# bpod_stepper_1_2.net
KiCad netlist of a schematic drawn in EAGLE
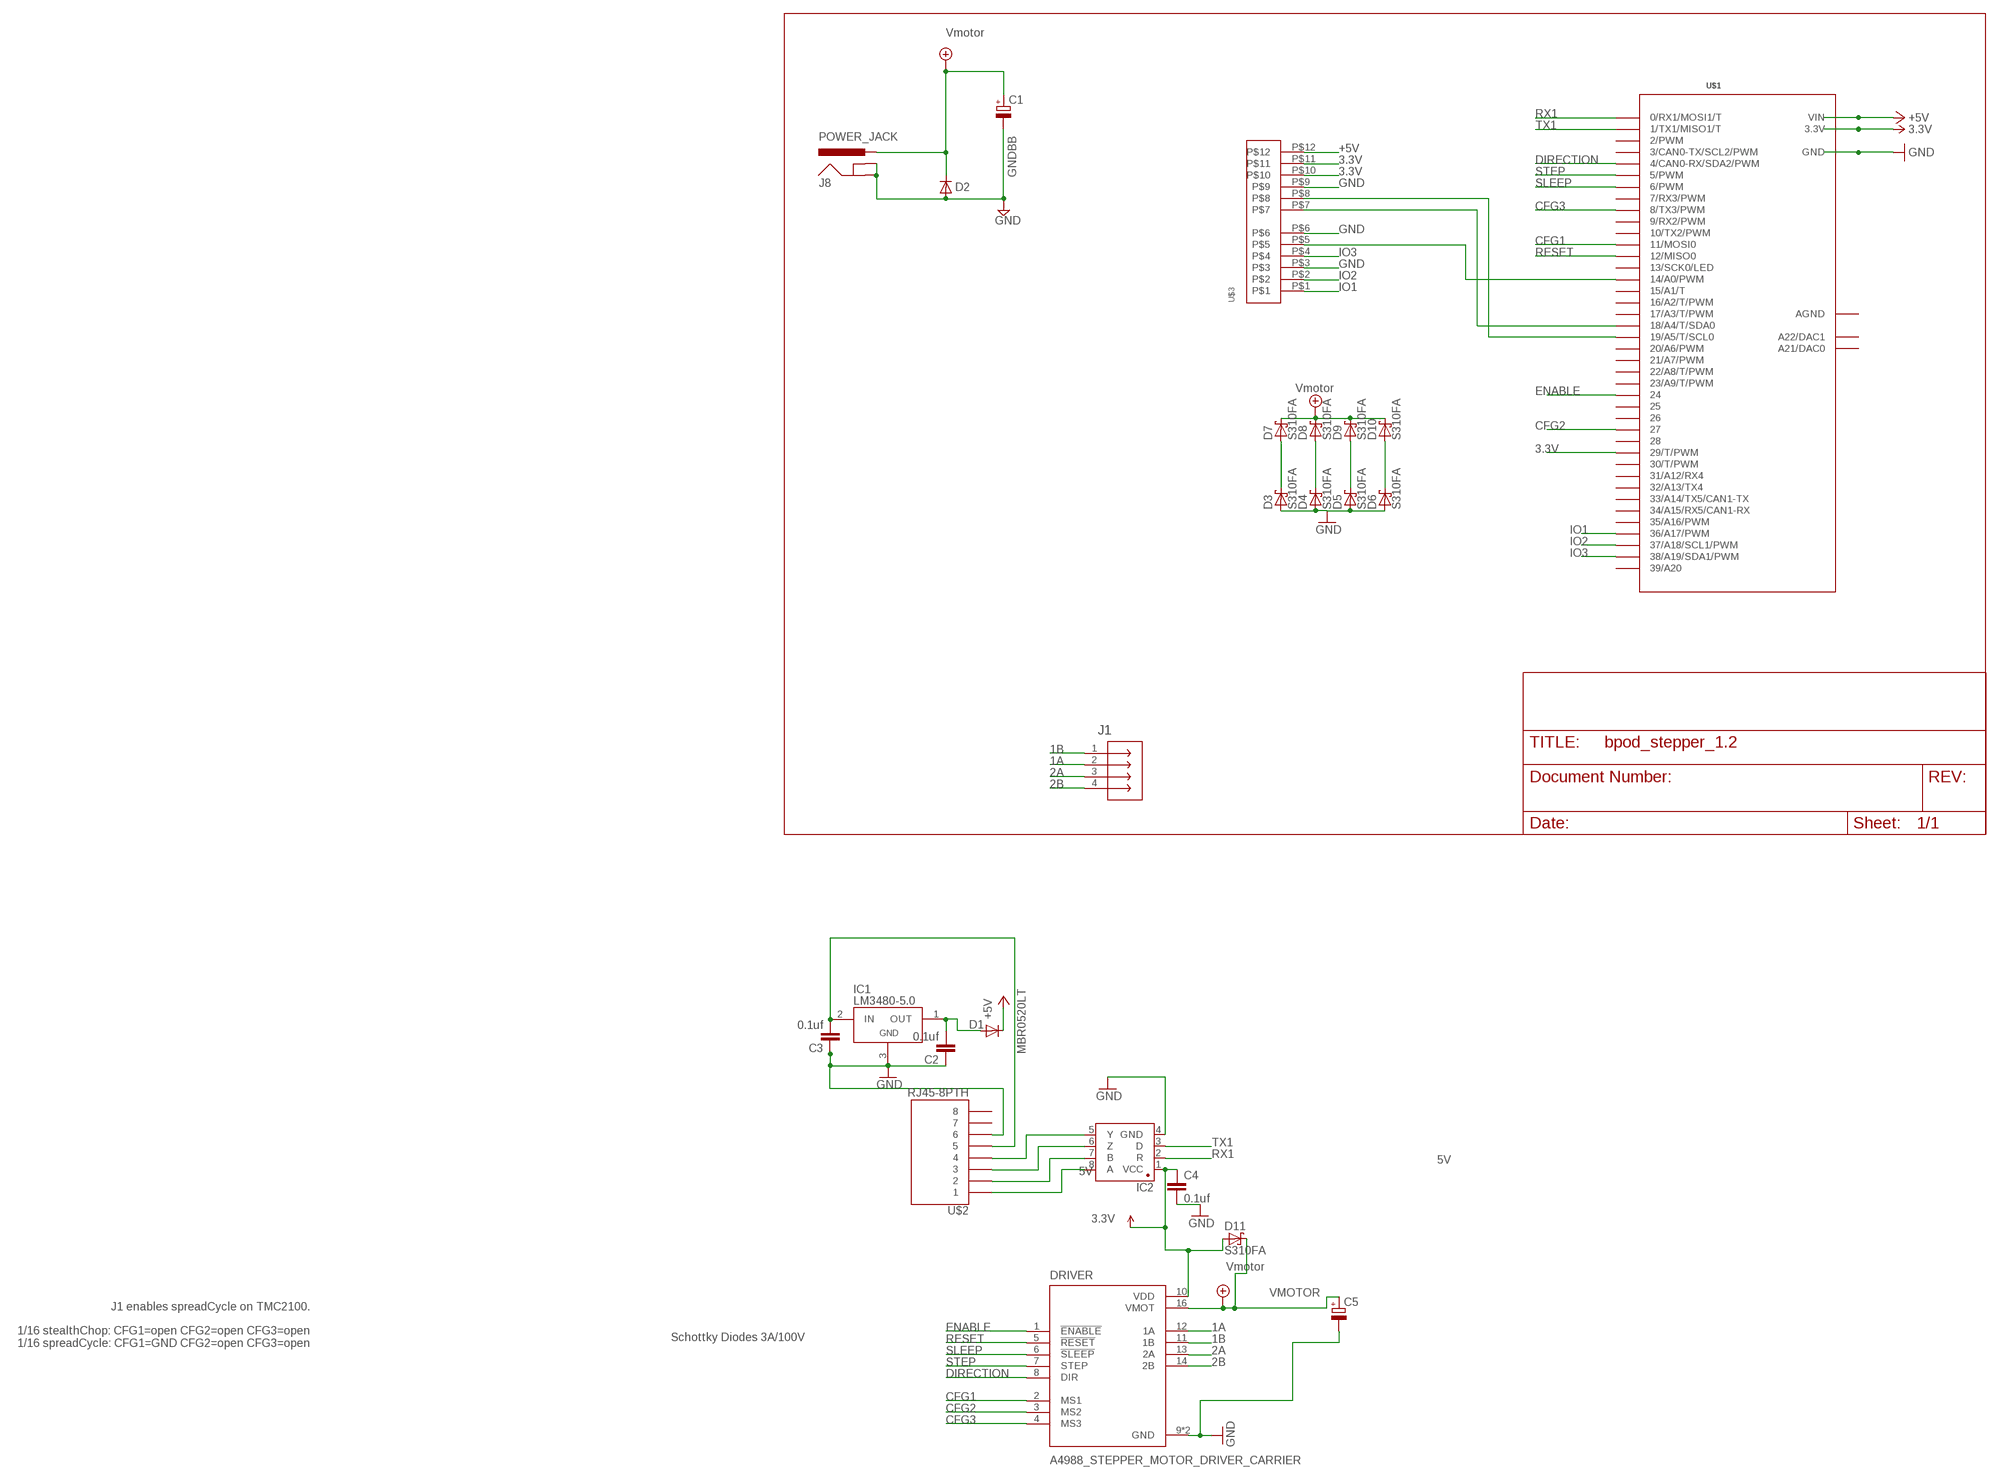
[diagram p0: schematic, sheet 1]

(export (version "E")
  (design (tool "Eeschema 10.0.6"))
  (components
    (comp (ref "C1")
      (value "CPOL-EUG")
      (footprint "eagle-import:PANASONIC_G")
      (libsource (lib "eagle-import") (part "CPOL-EUG"))
    )
    (comp (ref "C2")
      (value "0.1uf")
      (footprint "eagle-import:1206@1")
      (libsource (lib "eagle-import") (part "CAP1206"))
    )
    (comp (ref "C3")
      (value "0.1uf")
      (footprint "eagle-import:1206@1")
      (libsource (lib "eagle-import") (part "CAP1206"))
    )
    (comp (ref "C4")
      (value "0.1uf")
      (footprint "eagle-import:1206@1")
      (libsource (lib "eagle-import") (part "CAP1206"))
    )
    (comp (ref "C5")
      (value "CPOL-EUG")
      (footprint "eagle-import:PANASONIC_G")
      (libsource (lib "eagle-import") (part "CPOL-EUG"))
    )
    (comp (ref "D1")
      (value "MBR0520LT")
      (footprint "eagle-import:SOD123")
      (libsource (lib "eagle-import") (part "MBR0520LT"))
    )
    (comp (ref "D2")
      (value "DIODE-DO214AA")
      (footprint "eagle-import:DO214AA")
      (libsource (lib "eagle-import") (part "DIODE-DO214AA"))
    )
    (comp (ref "D3")
      (value "S310FA")
      (footprint "eagle-import:SOD123")
      (libsource (lib "eagle-import") (part "D_SCHOTTKY-SOD123"))
    )
    (comp (ref "D4")
      (value "S310FA")
      (footprint "eagle-import:SOD123")
      (libsource (lib "eagle-import") (part "D_SCHOTTKY-SOD123"))
    )
    (comp (ref "D5")
      (value "S310FA")
      (footprint "eagle-import:SOD123")
      (libsource (lib "eagle-import") (part "D_SCHOTTKY-SOD123"))
    )
    (comp (ref "D6")
      (value "S310FA")
      (footprint "eagle-import:SOD123")
      (libsource (lib "eagle-import") (part "D_SCHOTTKY-SOD123"))
    )
    (comp (ref "D7")
      (value "S310FA")
      (footprint "eagle-import:SOD123")
      (libsource (lib "eagle-import") (part "D_SCHOTTKY-SOD123"))
    )
    (comp (ref "D8")
      (value "S310FA")
      (footprint "eagle-import:SOD123")
      (libsource (lib "eagle-import") (part "D_SCHOTTKY-SOD123"))
    )
    (comp (ref "D9")
      (value "S310FA")
      (footprint "eagle-import:SOD123")
      (libsource (lib "eagle-import") (part "D_SCHOTTKY-SOD123"))
    )
    (comp (ref "D10")
      (value "S310FA")
      (footprint "eagle-import:SOD123")
      (libsource (lib "eagle-import") (part "D_SCHOTTKY-SOD123"))
    )
    (comp (ref "D11")
      (value "S310FA")
      (footprint "eagle-import:SOD123")
      (libsource (lib "eagle-import") (part "D_SCHOTTKY-SOD123"))
    )
    (comp (ref "DRIVER")
      (value "A4988_STEPPER_MOTOR_DRIVER_CARRIER")
      (footprint "eagle-import:MODULE_A4988_STEPPER_MOTOR_DRIVER_CARRIER")
      (fields (field (name "MF") "Pololu") (field (name "MP") "A4988 STEPPER MOTOR DRIVER CARRIER"))
      (libsource (lib "eagle-import") (part "A4988_STEPPER_MOTOR_DRIVER_CARRIER"))
    )
    (comp (ref "IC1")
      (value "LM3480-5.0")
      (footprint "eagle-import:SOT-23-3")
      (libsource (lib "eagle-import") (part "LM3480-5.0"))
    )
    (comp (ref "IC2")
      (value "SN65HVD31DR")
      (footprint "eagle-import:SO08")
      (libsource (lib "eagle-import") (part "SN65HVD31DR"))
    )
    (comp (ref "J1")
      (value "282841-4")
      (footprint "eagle-import:CONN4_282841-4_TEC")
      (fields (field (name "COPYRIGHT") "Copyright (C) 2018 Accelerated Designs. All rights reserved"))
      (libsource (lib "eagle-import") (part "282841-4"))
    )
    (comp (ref "J8")
      (value "POWER_JACK")
      (footprint "eagle-import:POWER_JACK_PTH")
      (libsource (lib "eagle-import") (part "POWER_JACK"))
    )
    (comp (ref "U$1")
      (value "TEENSY_3.6_DIL")
      (footprint "eagle-import:TEENSY_3.6_DIL")
      (libsource (lib "eagle-import") (part "TEENSY_3.6_DIL"))
    )
    (comp (ref "U$2")
      (value "RJ45-8PTH")
      (footprint "eagle-import:RJ45-8")
      (libsource (lib "eagle-import") (part "RJ45-8PTH"))
    )
    (comp (ref "U$3")
      (value "12POS_MOLEX_SOCKET")
      (footprint "eagle-import:12POS_MOLEX_SOCKET")
      (libsource (lib "eagle-import") (part "12POS_MOLEX_SOCKET"))
    )
  )
  (nets
    (net (code "1") (name "+5V") (class "Default")
      (node (ref "D1") (pin "C") (pinfunction "C_C") (pintype "passive"))
      (node (ref "U$1") (pin "VIN") (pinfunction "VIN_VIN") (pintype "power_in"))
      (node (ref "U$3") (pin "P$12") (pinfunction "P$12_P$12") (pintype "bidirectional"))
    )
    (net (code "2") (name "/1A") (class "Default")
      (node (ref "D4") (pin "C") (pinfunction "C_C") (pintype "passive"))
      (node (ref "D8") (pin "A") (pinfunction "A_A") (pintype "passive"))
      (node (ref "DRIVER") (pin "12") (pinfunction "1A_12") (pintype "output"))
      (node (ref "J1") (pin "2") (pinfunction "2_2") (pintype "passive"))
    )
    (net (code "3") (name "/1B") (class "Default")
      (node (ref "D3") (pin "C") (pinfunction "C_C") (pintype "passive"))
      (node (ref "D7") (pin "A") (pinfunction "A_A") (pintype "passive"))
      (node (ref "DRIVER") (pin "11") (pinfunction "1B_11") (pintype "output"))
      (node (ref "J1") (pin "1") (pinfunction "1_1") (pintype "passive"))
    )
    (net (code "4") (name "/2A") (class "Default")
      (node (ref "D5") (pin "C") (pinfunction "C_C") (pintype "passive"))
      (node (ref "D9") (pin "A") (pinfunction "A_A") (pintype "passive"))
      (node (ref "DRIVER") (pin "13") (pinfunction "2A_13") (pintype "output"))
      (node (ref "J1") (pin "3") (pinfunction "3_3") (pintype "passive"))
    )
    (net (code "5") (name "/2B") (class "Default")
      (node (ref "D10") (pin "A") (pinfunction "A_A") (pintype "passive"))
      (node (ref "D6") (pin "C") (pinfunction "C_C") (pintype "passive"))
      (node (ref "DRIVER") (pin "14") (pinfunction "2B_14") (pintype "output"))
      (node (ref "J1") (pin "4") (pinfunction "4_4") (pintype "passive"))
    )
    (net (code "6") (name "/AGND") (class "Default")
      (node (ref "U$1") (pin "AGND") (pinfunction "AGND_AGND") (pintype "power_in"))
    )
    (net (code "7") (name "/CFG1") (class "Default")
      (node (ref "DRIVER") (pin "2") (pinfunction "MS1_2") (pintype "input"))
      (node (ref "U$1") (pin "11") (pinfunction "11/MOSI0_11") (pintype "bidirectional"))
    )
    (net (code "8") (name "/CFG2") (class "Default")
      (node (ref "DRIVER") (pin "3") (pinfunction "MS2_3") (pintype "input"))
      (node (ref "U$1") (pin "27") (pinfunction "27_27") (pintype "bidirectional"))
    )
    (net (code "9") (name "/CFG3") (class "Default")
      (node (ref "DRIVER") (pin "4") (pinfunction "MS3_4") (pintype "input"))
      (node (ref "U$1") (pin "8") (pinfunction "8/TX3/PWM_8") (pintype "bidirectional"))
    )
    (net (code "10") (name "/DIRECTION") (class "Default")
      (node (ref "DRIVER") (pin "8") (pinfunction "DIR_8") (pintype "input"))
      (node (ref "U$1") (pin "4") (pinfunction "4/CAN0-RX/SDA2/PWM_4") (pintype "bidirectional"))
    )
    (net (code "11") (name "/ENABLE") (class "Default")
      (node (ref "DRIVER") (pin "1") (pinfunction "~{ENABLE}_1") (pintype "input"))
      (node (ref "U$1") (pin "24") (pinfunction "24_24") (pintype "bidirectional"))
    )
    (net (code "12") (name "/IO1") (class "Default")
      (node (ref "U$1") (pin "36/A17") (pinfunction "36/A17/PWM_36/A17") (pintype "bidirectional"))
      (node (ref "U$3") (pin "P$1") (pinfunction "P$1_P$1") (pintype "bidirectional"))
    )
    (net (code "13") (name "/IO2") (class "Default")
      (node (ref "U$1") (pin "37/A18") (pinfunction "37/A18/SCL1/PWM_37/A18") (pintype "bidirectional"))
      (node (ref "U$3") (pin "P$2") (pinfunction "P$2_P$2") (pintype "bidirectional"))
    )
    (net (code "14") (name "/IO3") (class "Default")
      (node (ref "U$1") (pin "38/A19") (pinfunction "38/A19/SDA1/PWM_38/A19") (pintype "bidirectional"))
      (node (ref "U$3") (pin "P$4") (pinfunction "P$4_P$4") (pintype "bidirectional"))
    )
    (net (code "15") (name "/RESET") (class "Default")
      (node (ref "DRIVER") (pin "5") (pinfunction "~{RESET}_5") (pintype "input"))
      (node (ref "U$1") (pin "12") (pinfunction "12/MISO0_12") (pintype "bidirectional"))
    )
    (net (code "16") (name "/RX1") (class "Default")
      (node (ref "IC2") (pin "2") (pinfunction "R_2") (pintype "bidirectional"))
      (node (ref "U$1") (pin "0") (pinfunction "0/RX1/MOSI1/T_0") (pintype "bidirectional"))
    )
    (net (code "17") (name "/SLEEP") (class "Default")
      (node (ref "DRIVER") (pin "6") (pinfunction "~{SLEEP}_6") (pintype "input"))
      (node (ref "U$1") (pin "6") (pinfunction "6/PWM_6") (pintype "bidirectional"))
    )
    (net (code "18") (name "/STEP") (class "Default")
      (node (ref "DRIVER") (pin "7") (pinfunction "STEP_7") (pintype "input"))
      (node (ref "U$1") (pin "5") (pinfunction "5/PWM_5") (pintype "bidirectional"))
    )
    (net (code "19") (name "/TX1") (class "Default")
      (node (ref "IC2") (pin "3") (pinfunction "D_3") (pintype "bidirectional"))
      (node (ref "U$1") (pin "1") (pinfunction "1/TX1/MISO1/T_1") (pintype "bidirectional"))
    )
    (net (code "20") (name "3.3V") (class "Default")
      (node (ref "C4") (pin "1") (pinfunction "1_1") (pintype "passive"))
      (node (ref "D11") (pin "A") (pinfunction "A_A") (pintype "passive"))
      (node (ref "DRIVER") (pin "10") (pinfunction "VDD_10") (pintype "power_in"))
      (node (ref "IC2") (pin "1") (pinfunction "VCC_1") (pintype "bidirectional"))
      (node (ref "U$1") (pin "29") (pinfunction "29/T/PWM_29") (pintype "bidirectional"))
      (node (ref "U$1") (pin "3.3V") (pinfunction "3.3V_3.3V") (pintype "power_in"))
      (node (ref "U$1") (pin "3.3V3") (pinfunction "3.3V_3.3V3") (pintype "power_in"))
      (node (ref "U$3") (pin "P$10") (pinfunction "P$10_P$10") (pintype "bidirectional"))
      (node (ref "U$3") (pin "P$11") (pinfunction "P$11_P$11") (pintype "bidirectional"))
    )
    (net (code "21") (name "GND") (class "Default")
      (node (ref "C1") (pin "-") (pinfunction "-_-") (pintype "passive"))
      (node (ref "C2") (pin "1") (pinfunction "1_1") (pintype "passive"))
      (node (ref "C3") (pin "1") (pinfunction "1_1") (pintype "passive"))
      (node (ref "C4") (pin "2") (pinfunction "2_2") (pintype "passive"))
      (node (ref "C5") (pin "-") (pinfunction "-_-") (pintype "passive"))
      (node (ref "D2") (pin "A") (pinfunction "A_A") (pintype "passive"))
      (node (ref "D3") (pin "A") (pinfunction "A_A") (pintype "passive"))
      (node (ref "D4") (pin "A") (pinfunction "A_A") (pintype "passive"))
      (node (ref "D5") (pin "A") (pinfunction "A_A") (pintype "passive"))
      (node (ref "D6") (pin "A") (pinfunction "A_A") (pintype "passive"))
      (node (ref "DRIVER") (pin "15") (pinfunction "GND_15") (pintype "power_in"))
      (node (ref "DRIVER") (pin "9") (pinfunction "GND_9") (pintype "power_in"))
      (node (ref "IC1") (pin "3") (pinfunction "GND_3") (pintype "power_in"))
      (node (ref "IC2") (pin "4") (pinfunction "GND_4") (pintype "bidirectional"))
      (node (ref "J8") (pin "GND") (pinfunction "GND_GND") (pintype "bidirectional"))
      (node (ref "J8") (pin "GNDBREAK") (pinfunction "GNDBREAK_GNDBREAK") (pintype "bidirectional"))
      (node (ref "U$1") (pin "GND") (pinfunction "GND_GND") (pintype "power_in"))
      (node (ref "U$1") (pin "GND1") (pinfunction "GND_GND1") (pintype "power_in"))
      (node (ref "U$2") (pin "6") (pinfunction "6_6") (pintype "bidirectional"))
      (node (ref "U$3") (pin "P$3") (pinfunction "P$3_P$3") (pintype "bidirectional"))
      (node (ref "U$3") (pin "P$6") (pinfunction "P$6_P$6") (pintype "bidirectional"))
      (node (ref "U$3") (pin "P$9") (pinfunction "P$9_P$9") (pintype "bidirectional"))
    )
    (net (code "22") (name "Net-(IC1-IN)") (class "Default")
      (node (ref "C3") (pin "2") (pinfunction "2_2") (pintype "passive"))
      (node (ref "IC1") (pin "2") (pinfunction "IN_2") (pintype "power_in"))
      (node (ref "U$2") (pin "5") (pinfunction "5_5") (pintype "bidirectional"))
    )
    (net (code "23") (name "Net-(IC1-OUT)") (class "Default")
      (node (ref "C2") (pin "2") (pinfunction "2_2") (pintype "passive"))
      (node (ref "D1") (pin "A") (pinfunction "A_A") (pintype "passive"))
      (node (ref "IC1") (pin "1") (pinfunction "OUT_1") (pintype "power_in"))
    )
    (net (code "24") (name "Net-(IC2-A)") (class "Default")
      (node (ref "IC2") (pin "8") (pinfunction "A_8") (pintype "bidirectional"))
      (node (ref "U$2") (pin "1") (pinfunction "1_1") (pintype "bidirectional"))
    )
    (net (code "25") (name "Net-(IC2-B)") (class "Default")
      (node (ref "IC2") (pin "7") (pinfunction "B_7") (pintype "bidirectional"))
      (node (ref "U$2") (pin "2") (pinfunction "2_2") (pintype "bidirectional"))
    )
    (net (code "26") (name "Net-(IC2-Y)") (class "Default")
      (node (ref "IC2") (pin "5") (pinfunction "Y_5") (pintype "bidirectional"))
      (node (ref "U$2") (pin "4") (pinfunction "4_4") (pintype "bidirectional"))
    )
    (net (code "27") (name "Net-(IC2-Z)") (class "Default")
      (node (ref "IC2") (pin "6") (pinfunction "Z_6") (pintype "bidirectional"))
      (node (ref "U$2") (pin "3") (pinfunction "3_3") (pintype "bidirectional"))
    )
    (net (code "28") (name "Net-(U$1-14{slash}A0{slash}PWM)") (class "Default")
      (node (ref "U$1") (pin "14/A0") (pinfunction "14/A0/PWM_14/A0") (pintype "bidirectional"))
      (node (ref "U$3") (pin "P$5") (pinfunction "P$5_P$5") (pintype "bidirectional"))
    )
    (net (code "29") (name "Net-(U$1-18{slash}A4{slash}T{slash}SDA0)") (class "Default")
      (node (ref "U$1") (pin "18/A4") (pinfunction "18/A4/T/SDA0_18/A4") (pintype "bidirectional"))
      (node (ref "U$3") (pin "P$7") (pinfunction "P$7_P$7") (pintype "bidirectional"))
    )
    (net (code "30") (name "Net-(U$1-19{slash}A5{slash}T{slash}SCL0)") (class "Default")
      (node (ref "U$1") (pin "19/A5") (pinfunction "19/A5/T/SCL0_19/A5") (pintype "bidirectional"))
      (node (ref "U$3") (pin "P$8") (pinfunction "P$8_P$8") (pintype "bidirectional"))
    )
    (net (code "31") (name "Vmotor") (class "Default")
      (node (ref "C1") (pin "+") (pinfunction "+_+") (pintype "passive"))
      (node (ref "C5") (pin "+") (pinfunction "+_+") (pintype "passive"))
      (node (ref "D10") (pin "C") (pinfunction "C_C") (pintype "passive"))
      (node (ref "D11") (pin "C") (pinfunction "C_C") (pintype "passive"))
      (node (ref "D2") (pin "C") (pinfunction "C_C") (pintype "passive"))
      (node (ref "D7") (pin "C") (pinfunction "C_C") (pintype "passive"))
      (node (ref "D8") (pin "C") (pinfunction "C_C") (pintype "passive"))
      (node (ref "D9") (pin "C") (pinfunction "C_C") (pintype "passive"))
      (node (ref "DRIVER") (pin "16") (pinfunction "VMOT_16") (pintype "power_in"))
      (node (ref "J8") (pin "PWR") (pinfunction "PWR_PWR") (pintype "bidirectional"))
    )
    (net (code "32") (name "unconnected-(U$1-2{slash}PWM-Pad2)") (class "Default")
      (node (ref "U$1") (pin "2") (pinfunction "2/PWM_2") (pintype "bidirectional"))
    )
    (net (code "33") (name "unconnected-(U$1-3{slash}CAN0-TX{slash}SCL2{slash}PWM-Pad3)") (class "Default")
      (node (ref "U$1") (pin "3") (pinfunction "3/CAN0-TX/SCL2/PWM_3") (pintype "bidirectional"))
    )
    (net (code "34") (name "unconnected-(U$1-7{slash}RX3{slash}PWM-Pad7)") (class "Default")
      (node (ref "U$1") (pin "7") (pinfunction "7/RX3/PWM_7") (pintype "bidirectional"))
    )
    (net (code "35") (name "unconnected-(U$1-9{slash}RX2{slash}PWM-Pad9)") (class "Default")
      (node (ref "U$1") (pin "9") (pinfunction "9/RX2/PWM_9") (pintype "bidirectional"))
    )
    (net (code "36") (name "unconnected-(U$1-10{slash}TX2{slash}PWM-Pad10)") (class "Default")
      (node (ref "U$1") (pin "10") (pinfunction "10/TX2/PWM_10") (pintype "bidirectional"))
    )
    (net (code "37") (name "unconnected-(U$1-13{slash}SCK0{slash}LED-Pad13)") (class "Default")
      (node (ref "U$1") (pin "13") (pinfunction "13/SCK0/LED_13") (pintype "bidirectional"))
    )
    (net (code "38") (name "unconnected-(U$1-15{slash}A1{slash}T-Pad15{slash}A1)") (class "Default")
      (node (ref "U$1") (pin "15/A1") (pinfunction "15/A1/T_15/A1") (pintype "bidirectional"))
    )
    (net (code "39") (name "unconnected-(U$1-16{slash}A2{slash}T{slash}PWM-Pad16{slash}A2)") (class "Default")
      (node (ref "U$1") (pin "16/A2") (pinfunction "16/A2/T/PWM_16/A2") (pintype "bidirectional"))
    )
    (net (code "40") (name "unconnected-(U$1-17{slash}A3{slash}T{slash}PWM-Pad17{slash}A3)") (class "Default")
      (node (ref "U$1") (pin "17/A3") (pinfunction "17/A3/T/PWM_17/A3") (pintype "bidirectional"))
    )
    (net (code "41") (name "unconnected-(U$1-20{slash}A6{slash}PWM-Pad20{slash}A6)") (class "Default")
      (node (ref "U$1") (pin "20/A6") (pinfunction "20/A6/PWM_20/A6") (pintype "bidirectional"))
    )
    (net (code "42") (name "unconnected-(U$1-21{slash}A7{slash}PWM-Pad21{slash}A7)") (class "Default")
      (node (ref "U$1") (pin "21/A7") (pinfunction "21/A7/PWM_21/A7") (pintype "bidirectional"))
    )
    (net (code "43") (name "unconnected-(U$1-22{slash}A8{slash}T{slash}PWM-Pad22{slash}A8)") (class "Default")
      (node (ref "U$1") (pin "22/A8") (pinfunction "22/A8/T/PWM_22/A8") (pintype "bidirectional"))
    )
    (net (code "44") (name "unconnected-(U$1-23{slash}A9{slash}T{slash}PWM-Pad23{slash}A9)") (class "Default")
      (node (ref "U$1") (pin "23/A9") (pinfunction "23/A9/T/PWM_23/A9") (pintype "bidirectional"))
    )
    (net (code "45") (name "unconnected-(U$1-30{slash}T{slash}PWM-Pad30)") (class "Default")
      (node (ref "U$1") (pin "30") (pinfunction "30/T/PWM_30") (pintype "bidirectional"))
    )
    (net (code "46") (name "unconnected-(U$1-31{slash}A12{slash}RX4-Pad31{slash}A12)") (class "Default")
      (node (ref "U$1") (pin "31/A12") (pinfunction "31/A12/RX4_31/A12") (pintype "bidirectional"))
    )
    (net (code "47") (name "unconnected-(U$1-32{slash}A13{slash}TX4-Pad32{slash}A13)") (class "Default")
      (node (ref "U$1") (pin "32/A13") (pinfunction "32/A13/TX4_32/A13") (pintype "bidirectional"))
    )
    (net (code "48") (name "unconnected-(U$1-33{slash}A14{slash}TX5{slash}CAN1-TX-Pad33{slash}A14)") (class "Default")
      (node (ref "U$1") (pin "33/A14") (pinfunction "33/A14/TX5/CAN1-TX_33/A14") (pintype "bidirectional"))
    )
    (net (code "49") (name "unconnected-(U$1-34{slash}A15{slash}RX5{slash}CAN1-RX-Pad34{slash}A15)") (class "Default")
      (node (ref "U$1") (pin "34/A15") (pinfunction "34/A15/RX5/CAN1-RX_34/A15") (pintype "bidirectional"))
    )
    (net (code "50") (name "unconnected-(U$1-35{slash}A16{slash}PWM-Pad35{slash}A16)") (class "Default")
      (node (ref "U$1") (pin "35/A16") (pinfunction "35/A16/PWM_35/A16") (pintype "bidirectional"))
    )
    (net (code "51") (name "unconnected-(U$1-A21{slash}DAC0-PadA21)") (class "Default")
      (node (ref "U$1") (pin "A21") (pinfunction "A21/DAC0_A21") (pintype "bidirectional"))
    )
    (net (code "52") (name "unconnected-(U$1-A22{slash}DAC1-PadA22)") (class "Default")
      (node (ref "U$1") (pin "A22") (pinfunction "A22/DAC1_A22") (pintype "bidirectional"))
    )
    (net (code "53") (name "unconnected-(U$1-Pad25)") (class "Default")
      (node (ref "U$1") (pin "25") (pinfunction "25_25") (pintype "bidirectional"))
    )
    (net (code "54") (name "unconnected-(U$1-Pad26)") (class "Default")
      (node (ref "U$1") (pin "26") (pinfunction "26_26") (pintype "bidirectional"))
    )
    (net (code "55") (name "unconnected-(U$1-Pad28)") (class "Default")
      (node (ref "U$1") (pin "28") (pinfunction "28_28") (pintype "bidirectional"))
    )
    (net (code "56") (name "unconnected-(U$1-Pad39{slash}A20)") (class "Default")
      (node (ref "U$1") (pin "39/A20") (pinfunction "39/A20_39/A20") (pintype "bidirectional"))
    )
    (net (code "57") (name "unconnected-(U$2-Pad7)") (class "Default")
      (node (ref "U$2") (pin "7") (pinfunction "7_7") (pintype "bidirectional"))
    )
    (net (code "58") (name "unconnected-(U$2-Pad8)") (class "Default")
      (node (ref "U$2") (pin "8") (pinfunction "8_8") (pintype "bidirectional"))
    )
  )
)
